# Diff_Amp_Shcematic.net
KiCad netlist of a schematic drawn in Altium Designer
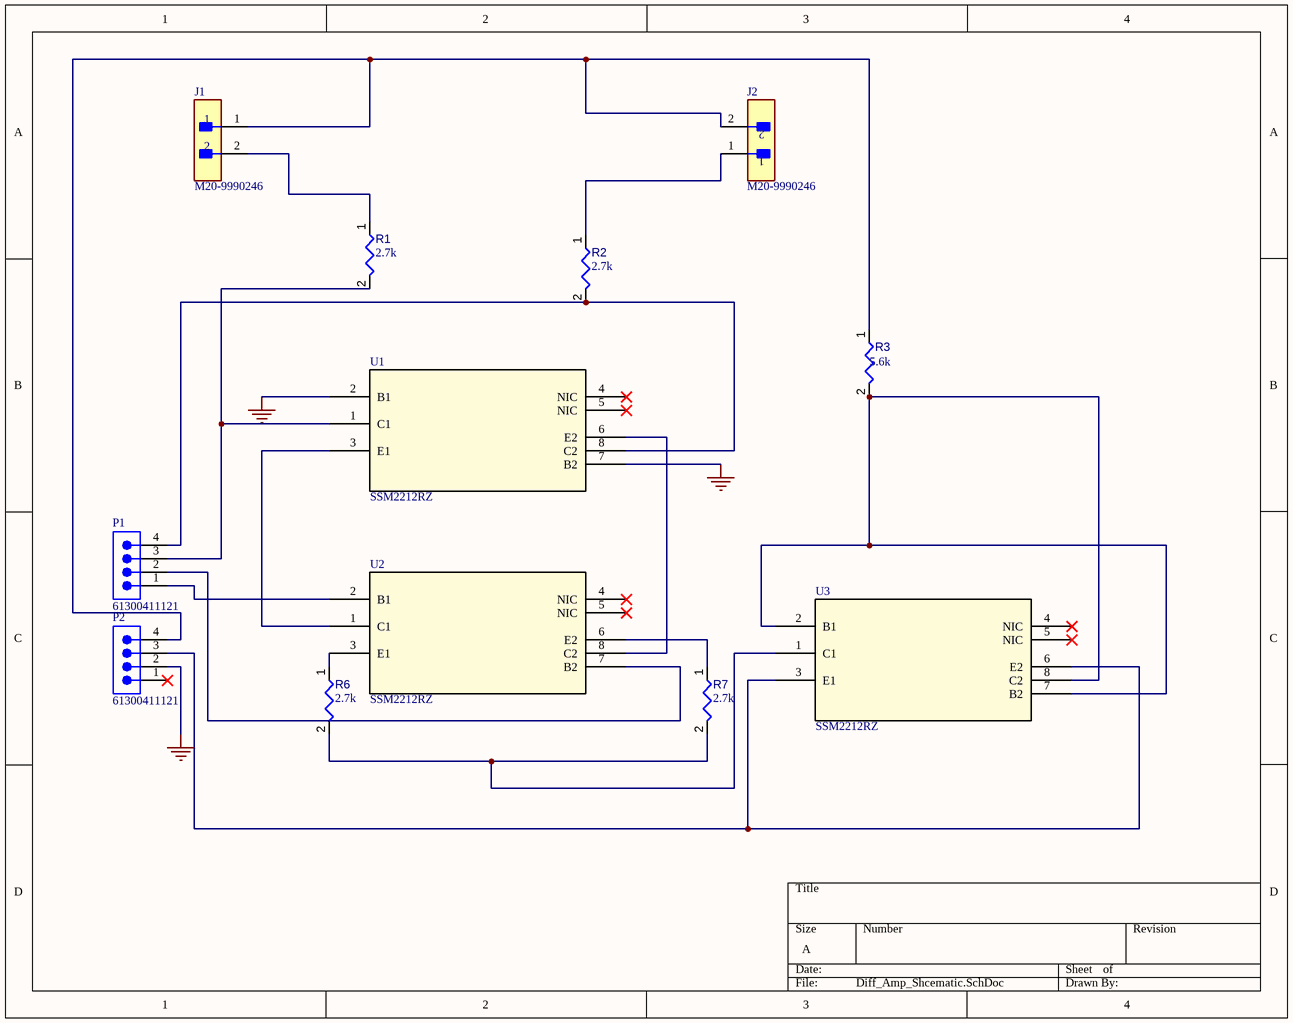
[diagram p0: Diff_Amp_Shcematic.SchDoc]

(export (version "E")
  (design (tool "Eeschema 10.0.6"))
  (components
    (comp (ref "J1")
      (value "M20-9990246")
      (footprint "FP-M20-9990246-MFG")
      (libsource (lib "University of Peradeniya") (part "3bc925449376181038e59eaffc5286c"))
    )
    (comp (ref "J2")
      (value "M20-9990246")
      (footprint "FP-M20-9990246-MFG")
      (libsource (lib "") (part "3bc925449376181038e59eaffc5286c_1"))
    )
    (comp (ref "P1")
      (value "61300411121")
      (footprint "61300411121")
      (libsource (lib "University of Peradeniya") (part "Header_Male_1R_04P"))
    )
    (comp (ref "P2")
      (value "61300411121")
      (footprint "61300411121")
      (libsource (lib "University of Peradeniya") (part "Header_Male_1R_04P"))
    )
    (comp (ref "R1")
      (value "2.7k")
      (footprint "FP-CRCW0805-e3-IPC_A")
      (fields
        (field (name "POWER") "125mW")
        (field (name "TOLERANCE") "1%")
        (field (name "Comment") "CRCW08052K70FKEA")
      )
      (libsource (lib "University of Peradeniya") (part "RES-2"))
    )
    (comp (ref "R2")
      (value "2.7k")
      (footprint "FP-CRCW0805-e3-IPC_A")
      (fields
        (field (name "POWER") "125mW")
        (field (name "TOLERANCE") "1%")
        (field (name "Comment") "CRCW08052K70FKEA")
      )
      (libsource (lib "University of Peradeniya") (part "RES-2"))
    )
    (comp (ref "R3")
      (value "5.6k")
      (footprint "FP-CRCW0805-e3-IPC_A")
      (fields
        (field (name "POWER") "125mW")
        (field (name "TOLERANCE") "1%")
        (field (name "Comment") "CRCW08052K70FKEA")
      )
      (libsource (lib "University of Peradeniya") (part "RES-2"))
    )
    (comp (ref "R6")
      (value "2.7k")
      (footprint "FP-CRCW0805-e3-IPC_A")
      (fields
        (field (name "POWER") "125mW")
        (field (name "TOLERANCE") "1%")
        (field (name "Comment") "CRCW08052K70FKEA")
      )
      (libsource (lib "University of Peradeniya") (part "RES-2"))
    )
    (comp (ref "R7")
      (value "2.7k")
      (footprint "FP-CRCW0805-e3-IPC_A")
      (fields
        (field (name "POWER") "125mW")
        (field (name "TOLERANCE") "1%")
        (field (name "Comment") "CRCW08052K70FKEA")
      )
      (libsource (lib "University of Peradeniya") (part "RES-2"))
    )
    (comp (ref "U1")
      (value "SSM2212RZ")
      (footprint "R_8_ADI")
      (description "No Description Available")
      (libsource (lib "University of Peradeniya") (part "SSM2212RZ"))
    )
    (comp (ref "U2")
      (value "SSM2212RZ")
      (footprint "R_8_ADI")
      (description "No Description Available")
      (libsource (lib "University of Peradeniya") (part "SSM2212RZ"))
    )
    (comp (ref "U3")
      (value "SSM2212RZ")
      (footprint "R_8_ADI")
      (description "No Description Available")
      (libsource (lib "University of Peradeniya") (part "SSM2212RZ"))
    )
  )
  (nets
    (net (code "1") (name "GND") (class "Default")
      (node (ref "P2") (pin "2") (pinfunction "2_2") (pintype "passive"))
      (node (ref "U1") (pin "2") (pinfunction "B1_2") (pintype "passive"))
      (node (ref "U1") (pin "7") (pinfunction "B2_7") (pintype "passive"))
    )
    (net (code "2") (name "Net-(J1-Pad1)") (class "Default")
      (node (ref "J1") (pin "1") (pinfunction "1_1") (pintype "passive"))
      (node (ref "J2") (pin "2") (pinfunction "2_2") (pintype "passive"))
      (node (ref "P2") (pin "4") (pinfunction "4_4") (pintype "passive"))
      (node (ref "R3") (pin "1") (pinfunction "1_1") (pintype "passive"))
    )
    (net (code "3") (name "Net-(J1-Pad2)") (class "Default")
      (node (ref "J1") (pin "2") (pinfunction "2_2") (pintype "passive"))
      (node (ref "R1") (pin "1") (pinfunction "1_1") (pintype "passive"))
    )
    (net (code "4") (name "Net-(J2-Pad1)") (class "Default")
      (node (ref "J2") (pin "1") (pinfunction "1_1") (pintype "passive"))
      (node (ref "R2") (pin "1") (pinfunction "1_1") (pintype "passive"))
    )
    (net (code "5") (name "Net-(U1-C1)") (class "Default")
      (node (ref "P1") (pin "3") (pinfunction "3_3") (pintype "passive"))
      (node (ref "R1") (pin "2") (pinfunction "2_2") (pintype "passive"))
      (node (ref "U1") (pin "1") (pinfunction "C1_1") (pintype "passive"))
    )
    (net (code "6") (name "Net-(U1-C2)") (class "Default")
      (node (ref "P1") (pin "4") (pinfunction "4_4") (pintype "passive"))
      (node (ref "R2") (pin "2") (pinfunction "2_2") (pintype "passive"))
      (node (ref "U1") (pin "8") (pinfunction "C2_8") (pintype "passive"))
    )
    (net (code "7") (name "Net-(U1-E1)") (class "Default")
      (node (ref "U1") (pin "3") (pinfunction "E1_3") (pintype "passive"))
      (node (ref "U2") (pin "1") (pinfunction "C1_1") (pintype "passive"))
    )
    (net (code "8") (name "Net-(U1-E2)") (class "Default")
      (node (ref "U1") (pin "6") (pinfunction "E2_6") (pintype "passive"))
      (node (ref "U2") (pin "8") (pinfunction "C2_8") (pintype "passive"))
    )
    (net (code "9") (name "Net-(U2-B1)") (class "Default")
      (node (ref "P1") (pin "1") (pinfunction "1_1") (pintype "passive"))
      (node (ref "U2") (pin "2") (pinfunction "B1_2") (pintype "passive"))
    )
    (net (code "10") (name "Net-(U2-B2)") (class "Default")
      (node (ref "P1") (pin "2") (pinfunction "2_2") (pintype "passive"))
      (node (ref "U2") (pin "7") (pinfunction "B2_7") (pintype "passive"))
    )
    (net (code "11") (name "Net-(U2-E1)") (class "Default")
      (node (ref "R6") (pin "1") (pinfunction "1_1") (pintype "passive"))
      (node (ref "U2") (pin "3") (pinfunction "E1_3") (pintype "passive"))
    )
    (net (code "12") (name "Net-(U2-E2)") (class "Default")
      (node (ref "R7") (pin "1") (pinfunction "1_1") (pintype "passive"))
      (node (ref "U2") (pin "6") (pinfunction "E2_6") (pintype "passive"))
    )
    (net (code "13") (name "Net-(U3-B1)") (class "Default")
      (node (ref "R3") (pin "2") (pinfunction "2_2") (pintype "passive"))
      (node (ref "U3") (pin "2") (pinfunction "B1_2") (pintype "passive"))
      (node (ref "U3") (pin "7") (pinfunction "B2_7") (pintype "passive"))
      (node (ref "U3") (pin "8") (pinfunction "C2_8") (pintype "passive"))
    )
    (net (code "14") (name "Net-(U3-C1)") (class "Default")
      (node (ref "R6") (pin "2") (pinfunction "2_2") (pintype "passive"))
      (node (ref "R7") (pin "2") (pinfunction "2_2") (pintype "passive"))
      (node (ref "U3") (pin "1") (pinfunction "C1_1") (pintype "passive"))
    )
    (net (code "15") (name "Net-(U3-E1)") (class "Default")
      (node (ref "P2") (pin "3") (pinfunction "3_3") (pintype "passive"))
      (node (ref "U3") (pin "3") (pinfunction "E1_3") (pintype "passive"))
      (node (ref "U3") (pin "6") (pinfunction "E2_6") (pintype "passive"))
    )
    (net (code "16") (name "unconnected-(P2-Pad1)") (class "Default")
      (node (ref "P2") (pin "1") (pinfunction "1_1") (pintype "passive+no_connect"))
    )
    (net (code "17") (name "unconnected-(U1-NIC-Pad4)") (class "Default")
      (node (ref "U1") (pin "4") (pinfunction "NIC_4") (pintype "passive+no_connect"))
    )
    (net (code "18") (name "unconnected-(U1-NIC-Pad5)") (class "Default")
      (node (ref "U1") (pin "5") (pinfunction "NIC_5") (pintype "passive+no_connect"))
    )
    (net (code "19") (name "unconnected-(U2-NIC-Pad4)") (class "Default")
      (node (ref "U2") (pin "4") (pinfunction "NIC_4") (pintype "passive+no_connect"))
    )
    (net (code "20") (name "unconnected-(U2-NIC-Pad5)") (class "Default")
      (node (ref "U2") (pin "5") (pinfunction "NIC_5") (pintype "passive+no_connect"))
    )
    (net (code "21") (name "unconnected-(U3-NIC-Pad4)") (class "Default")
      (node (ref "U3") (pin "4") (pinfunction "NIC_4") (pintype "passive+no_connect"))
    )
    (net (code "22") (name "unconnected-(U3-NIC-Pad5)") (class "Default")
      (node (ref "U3") (pin "5") (pinfunction "NIC_5") (pintype "passive+no_connect"))
    )
  )
)
